# bitfury_power.net
KiCad netlist of a schematic drawn in Altium Designer
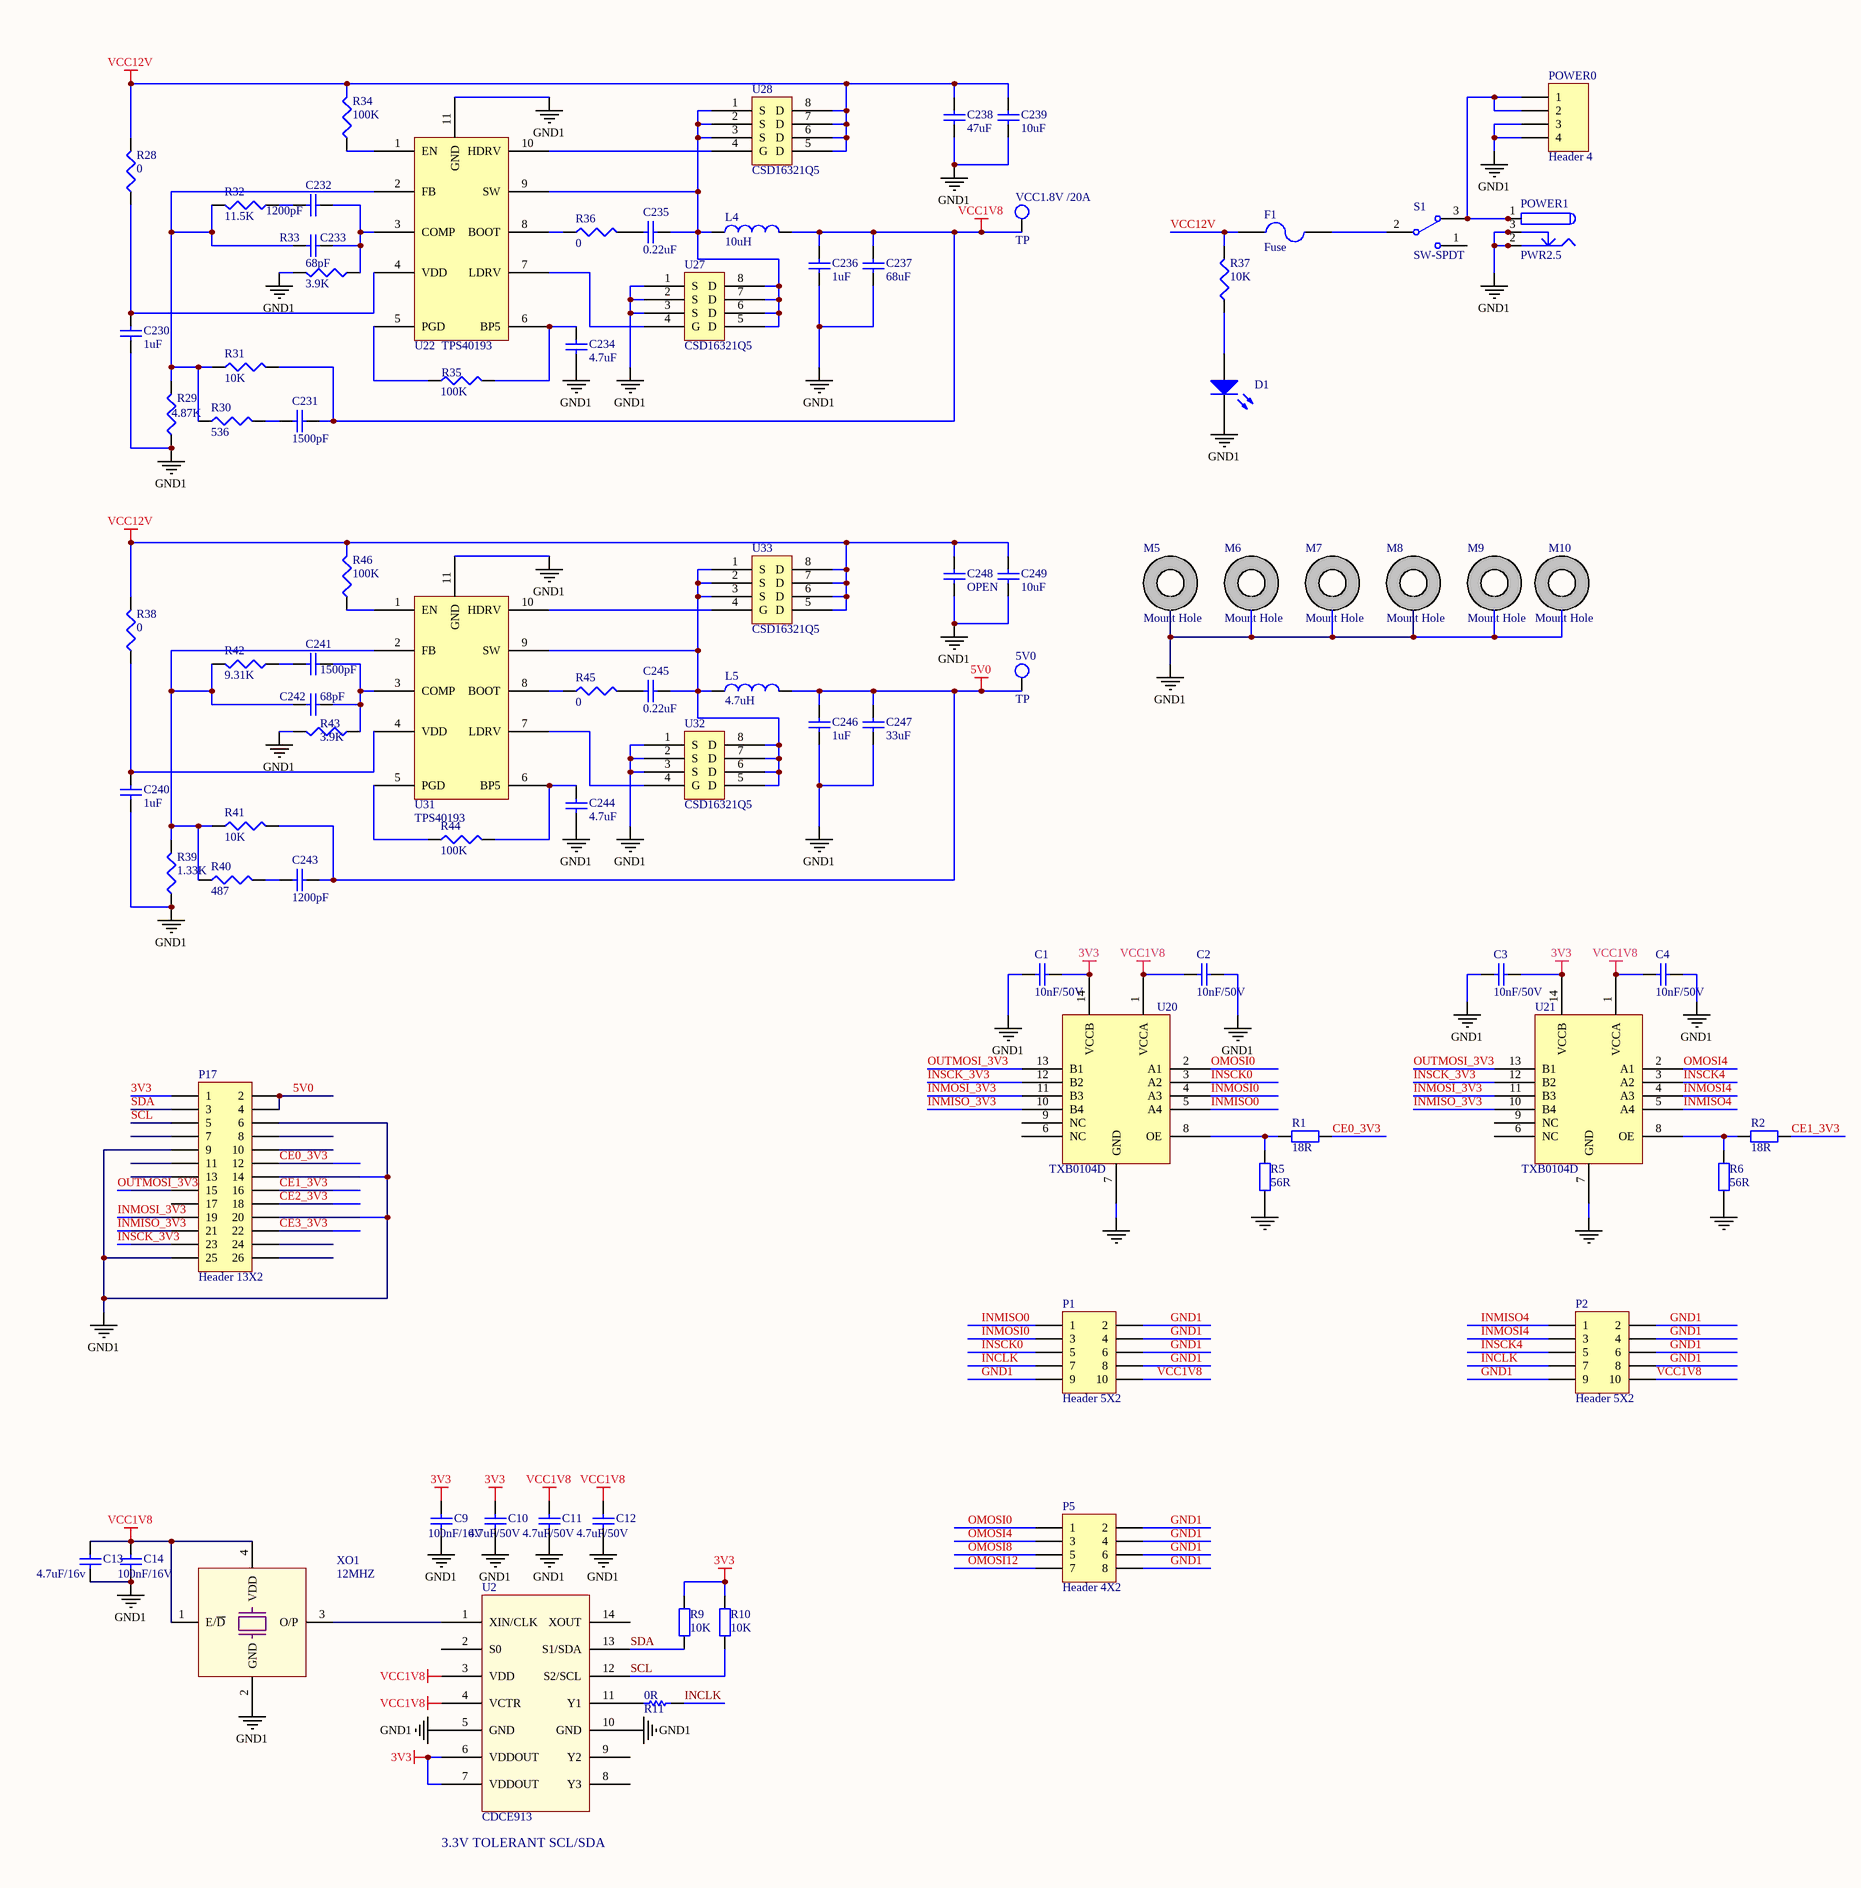
[diagram p0: bitfury_power.SchDoc, left]
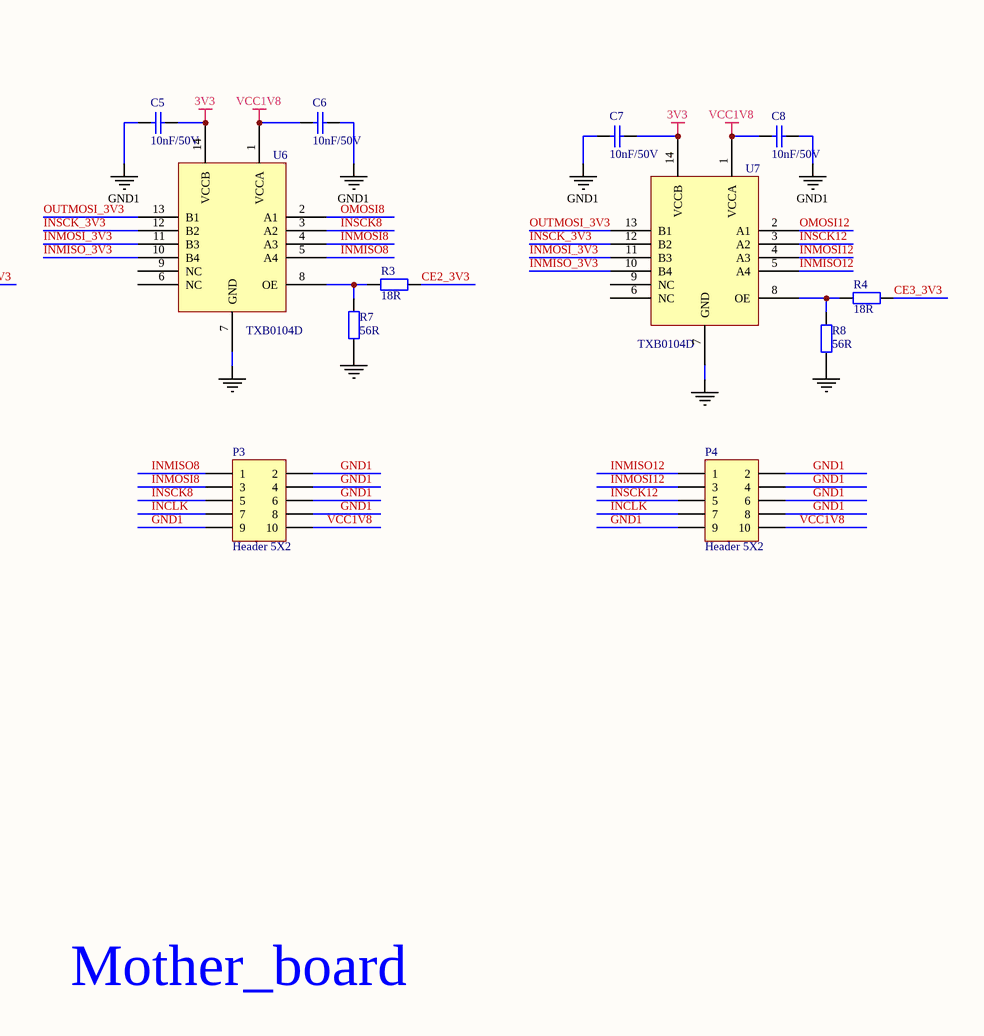
[diagram p1: bitfury_power.SchDoc, right]

(export (version "E")
  (design (tool "Eeschema 10.0.6"))
  (components
    (comp (ref "5V0") (value "TP") (footprint "PIN1") (libsource (lib "S6") (part "TP")))
    (comp (ref "C1")
      (value "10nF/50V")
      (footprint "1608[0603]")
      (description "Capacitor")
      (fields (field (name "PUBLISHER") "Altium Limited"))
      (libsource (lib "Miscellaneous Devices") (part "Cap"))
    )
    (comp (ref "C2")
      (value "10nF/50V")
      (footprint "1608[0603]")
      (description "Capacitor")
      (fields (field (name "PUBLISHER") "Altium Limited"))
      (libsource (lib "Miscellaneous Devices") (part "Cap"))
    )
    (comp (ref "C3")
      (value "10nF/50V")
      (footprint "1608[0603]")
      (description "Capacitor")
      (fields (field (name "PUBLISHER") "Altium Limited"))
      (libsource (lib "Miscellaneous Devices") (part "Cap"))
    )
    (comp (ref "C4")
      (value "10nF/50V")
      (footprint "1608[0603]")
      (description "Capacitor")
      (fields (field (name "PUBLISHER") "Altium Limited"))
      (libsource (lib "Miscellaneous Devices") (part "Cap"))
    )
    (comp (ref "C5")
      (value "10nF/50V")
      (footprint "1608[0603]")
      (description "Capacitor")
      (fields (field (name "PUBLISHER") "Altium Limited"))
      (libsource (lib "Miscellaneous Devices") (part "Cap"))
    )
    (comp (ref "C6")
      (value "10nF/50V")
      (footprint "1608[0603]")
      (description "Capacitor")
      (fields (field (name "PUBLISHER") "Altium Limited"))
      (libsource (lib "Miscellaneous Devices") (part "Cap"))
    )
    (comp (ref "C7")
      (value "10nF/50V")
      (footprint "1608[0603]")
      (description "Capacitor")
      (fields (field (name "PUBLISHER") "Altium Limited"))
      (libsource (lib "Miscellaneous Devices") (part "Cap"))
    )
    (comp (ref "C8")
      (value "10nF/50V")
      (footprint "1608[0603]")
      (description "Capacitor")
      (fields (field (name "PUBLISHER") "Altium Limited"))
      (libsource (lib "Miscellaneous Devices") (part "Cap"))
    )
    (comp (ref "C9")
      (value "100nF/16V")
      (footprint "1608[0603]")
      (description "Capacitor")
      (fields (field (name "PUBLISHER") "Altium Limited"))
      (libsource (lib "Miscellaneous Devices") (part "Cap"))
    )
    (comp (ref "C10")
      (value "4.7uF/50V")
      (footprint "1608[0603]")
      (description "Capacitor")
      (fields (field (name "PUBLISHER") "Altium Limited"))
      (libsource (lib "Miscellaneous Devices") (part "Cap"))
    )
    (comp (ref "C11")
      (value "4.7uF/50V")
      (footprint "1608[0603]")
      (description "Capacitor")
      (fields (field (name "PUBLISHER") "Altium Limited"))
      (libsource (lib "Miscellaneous Devices") (part "Cap"))
    )
    (comp (ref "C12")
      (value "4.7uF/50V")
      (footprint "1608[0603]")
      (description "Capacitor")
      (fields (field (name "PUBLISHER") "Altium Limited"))
      (libsource (lib "Miscellaneous Devices") (part "Cap"))
    )
    (comp (ref "C13")
      (value "4.7uF/16v")
      (footprint "1608[0603]")
      (description "Capacitor")
      (fields (field (name "PUBLISHER") "Altium Limited"))
      (libsource (lib "Miscellaneous Devices") (part "Cap"))
    )
    (comp (ref "C14")
      (value "100nF/16V")
      (footprint "1608[0603]")
      (description "Capacitor")
      (fields (field (name "PUBLISHER") "Altium Limited"))
      (libsource (lib "Miscellaneous Devices") (part "Cap"))
    )
    (comp (ref "C230")
      (value "1uF")
      (footprint "1608[0603]")
      (description "Capacitor")
      (fields (field (name "PUBLISHER") "Altium Limited"))
      (libsource (lib "Miscellaneous Devices") (part "Cap"))
    )
    (comp (ref "C231")
      (value "1500pF")
      (footprint "1608[0603]")
      (description "Capacitor")
      (fields (field (name "PUBLISHER") "Altium Limited"))
      (libsource (lib "Miscellaneous Devices") (part "Cap"))
    )
    (comp (ref "C232")
      (value "1200pF")
      (footprint "1608[0603]")
      (description "Capacitor")
      (fields (field (name "PUBLISHER") "Altium Limited"))
      (libsource (lib "Miscellaneous Devices") (part "Cap"))
    )
    (comp (ref "C233")
      (value "68pF")
      (footprint "1608[0603]")
      (description "Capacitor")
      (fields (field (name "PUBLISHER") "Altium Limited"))
      (libsource (lib "Miscellaneous Devices") (part "Cap"))
    )
    (comp (ref "C234")
      (value "4.7uF")
      (footprint "1608[0603]")
      (description "Capacitor")
      (fields (field (name "PUBLISHER") "Altium Limited"))
      (libsource (lib "Miscellaneous Devices") (part "Cap"))
    )
    (comp (ref "C235")
      (value "0.22uF")
      (footprint "1608[0603]")
      (description "Capacitor")
      (fields (field (name "PUBLISHER") "Altium Limited"))
      (libsource (lib "Miscellaneous Devices") (part "Cap"))
    )
    (comp (ref "C236")
      (value "1uF")
      (footprint "1608[0603]")
      (description "Capacitor")
      (fields (field (name "PUBLISHER") "Altium Limited"))
      (libsource (lib "Miscellaneous Devices") (part "Cap"))
    )
    (comp (ref "C237")
      (value "68uF")
      (footprint "C1210")
      (description "Capacitor")
      (fields (field (name "PUBLISHER") "Altium Limited"))
      (libsource (lib "Miscellaneous Devices") (part "Cap"))
    )
    (comp (ref "C238")
      (value "47uF")
      (footprint "C1210")
      (description "Capacitor")
      (fields (field (name "PUBLISHER") "Altium Limited"))
      (libsource (lib "Miscellaneous Devices") (part "Cap"))
    )
    (comp (ref "C239")
      (value "10uF")
      (footprint "C1210")
      (description "Capacitor")
      (fields (field (name "PUBLISHER") "Altium Limited"))
      (libsource (lib "Miscellaneous Devices") (part "Cap"))
    )
    (comp (ref "C240")
      (value "1uF")
      (footprint "1608[0603]")
      (description "Capacitor")
      (fields (field (name "PUBLISHER") "Altium Limited"))
      (libsource (lib "Miscellaneous Devices") (part "Cap"))
    )
    (comp (ref "C241")
      (value "1500pF")
      (footprint "1608[0603]")
      (description "Capacitor")
      (fields (field (name "PUBLISHER") "Altium Limited"))
      (libsource (lib "Miscellaneous Devices") (part "Cap"))
    )
    (comp (ref "C242")
      (value "68pF")
      (footprint "1608[0603]")
      (description "Capacitor")
      (fields (field (name "PUBLISHER") "Altium Limited"))
      (libsource (lib "Miscellaneous Devices") (part "Cap"))
    )
    (comp (ref "C243")
      (value "1200pF")
      (footprint "1608[0603]")
      (description "Capacitor")
      (fields (field (name "PUBLISHER") "Altium Limited"))
      (libsource (lib "Miscellaneous Devices") (part "Cap"))
    )
    (comp (ref "C244")
      (value "4.7uF")
      (footprint "1608[0603]")
      (description "Capacitor")
      (fields (field (name "PUBLISHER") "Altium Limited"))
      (libsource (lib "Miscellaneous Devices") (part "Cap"))
    )
    (comp (ref "C245")
      (value "0.22uF")
      (footprint "1608[0603]")
      (description "Capacitor")
      (fields (field (name "PUBLISHER") "Altium Limited"))
      (libsource (lib "Miscellaneous Devices") (part "Cap"))
    )
    (comp (ref "C246")
      (value "1uF")
      (footprint "1608[0603]")
      (description "Capacitor")
      (fields (field (name "PUBLISHER") "Altium Limited"))
      (libsource (lib "Miscellaneous Devices") (part "Cap"))
    )
    (comp (ref "C247")
      (value "33uF")
      (footprint "C1210")
      (description "Capacitor")
      (fields (field (name "PUBLISHER") "Altium Limited"))
      (libsource (lib "Miscellaneous Devices") (part "Cap"))
    )
    (comp (ref "C248")
      (value "OPEN")
      (footprint "C1210")
      (description "Capacitor")
      (fields (field (name "PUBLISHER") "Altium Limited"))
      (libsource (lib "Miscellaneous Devices") (part "Cap"))
    )
    (comp (ref "C249")
      (value "10uF")
      (footprint "C1210")
      (description "Capacitor")
      (fields (field (name "PUBLISHER") "Altium Limited"))
      (libsource (lib "Miscellaneous Devices") (part "Cap"))
    )
    (comp (ref "D1")
      (value "~")
      (footprint "CD1608-0603")
      (description "Typical BLUE SiC LED")
      (fields (field (name "PUBLISHER") "Altium Limited"))
      (libsource (lib "Miscellaneous Devices") (part "LED3"))
    )
    (comp (ref "F1")
      (value "Fuse")
      (footprint "RESC5025N1")
      (fields (field (name "PUBLISHER") "Altium Limited"))
      (libsource (lib "Miscellaneous Devices") (part "Fuse 2"))
    )
    (comp (ref "L4")
      (value "10uH")
      (footprint "CDRH104RNP-120")
      (description "Inductor")
      (fields (field (name "PUBLISHER") "Altium Limited"))
      (libsource (lib "Miscellaneous Devices") (part "Inductor"))
    )
    (comp (ref "L5")
      (value "4.7uH")
      (footprint "CDRH104RNP-120")
      (description "Inductor")
      (fields (field (name "PUBLISHER") "Altium Limited"))
      (libsource (lib "Miscellaneous Devices") (part "Inductor"))
    )
    (comp (ref "M5") (value "Mount Hole") (footprint "MHOLE2") (libsource (lib "S6_2") (part "M_Hole")))
    (comp (ref "M6") (value "Mount Hole") (footprint "MHOLE2") (libsource (lib "S6_2") (part "M_Hole")))
    (comp (ref "M7") (value "Mount Hole") (footprint "MHOLE2") (libsource (lib "S6_2") (part "M_Hole")))
    (comp (ref "M8") (value "Mount Hole") (footprint "MHOLE2") (libsource (lib "S6_2") (part "M_Hole")))
    (comp (ref "M9") (value "Mount Hole") (footprint "MHOLE2") (libsource (lib "S6_2") (part "M_Hole")))
    (comp (ref "M10") (value "Mount Hole") (footprint "MHOLE2") (libsource (lib "S6_2") (part "M_Hole")))
    (comp (ref "P1")
      (value "Header 5X2")
      (footprint "HDR2X5")
      (description "Header, 5-Pin, Dual row")
      (fields (field (name "PUBLISHER") "Altium Limited"))
      (libsource (lib "Miscellaneous Connectors") (part "Header 5X2"))
    )
    (comp (ref "P2")
      (value "Header 5X2")
      (footprint "HDR2X5")
      (description "Header, 5-Pin, Dual row")
      (fields (field (name "PUBLISHER") "Altium Limited"))
      (libsource (lib "Miscellaneous Connectors") (part "Header 5X2"))
    )
    (comp (ref "P3")
      (value "Header 5X2")
      (footprint "HDR2X5")
      (description "Header, 5-Pin, Dual row")
      (fields (field (name "PUBLISHER") "Altium Limited"))
      (libsource (lib "Miscellaneous Connectors") (part "Header 5X2"))
    )
    (comp (ref "P4")
      (value "Header 5X2")
      (footprint "HDR2X5")
      (description "Header, 5-Pin, Dual row")
      (fields (field (name "PUBLISHER") "Altium Limited"))
      (libsource (lib "Miscellaneous Connectors") (part "Header 5X2"))
    )
    (comp (ref "P5")
      (value "Header 4X2")
      (footprint "HDR2X4")
      (description "Header, 4-Pin, Dual row")
      (fields (field (name "PUBLISHER") "Altium Limited"))
      (libsource (lib "Miscellaneous Connectors") (part "Header 4X2"))
    )
    (comp (ref "P17")
      (value "Header 13X2")
      (footprint "HDR2X13")
      (description "Header, 13-Pin, Dual row")
      (fields (field (name "PUBLISHER") "Altium Limited"))
      (libsource (lib "Miscellaneous Connectors") (part "Header 13X2"))
    )
    (comp (ref "POWER0")
      (value "Header 4")
      (footprint "SIP4")
      (description "Header, 4-Pin")
      (fields (field (name "PUBLISHER") "Altium Limited"))
      (libsource (lib "Miscellaneous Connectors") (part "Header 4"))
    )
    (comp (ref "POWER1")
      (value "PWR2.5")
      (footprint "KLD-0202")
      (description "Low Voltage Power Supply Connector")
      (fields (field (name "PUBLISHER") "Altium Limited"))
      (libsource (lib "Miscellaneous Connectors") (part "PWR2.5"))
    )
    (comp (ref "R1")
      (value "18R")
      (footprint "6-0805_L")
      (description "Resistor")
      (fields (field (name "PUBLISHER") "Altium Limited"))
      (libsource (lib "") (part "Res2_1"))
    )
    (comp (ref "R2")
      (value "18R")
      (footprint "6-0805_L")
      (description "Resistor")
      (fields (field (name "PUBLISHER") "Altium Limited"))
      (libsource (lib "") (part "Res2_1"))
    )
    (comp (ref "R3")
      (value "18R")
      (footprint "6-0805_L")
      (description "Resistor")
      (fields (field (name "PUBLISHER") "Altium Limited"))
      (libsource (lib "") (part "Res2_1"))
    )
    (comp (ref "R4")
      (value "18R")
      (footprint "6-0805_L")
      (description "Resistor")
      (fields (field (name "PUBLISHER") "Altium Limited"))
      (libsource (lib "") (part "Res2_1"))
    )
    (comp (ref "R5")
      (value "56R")
      (footprint "6-0805_L")
      (description "Resistor")
      (fields (field (name "PUBLISHER") "Altium Limited"))
      (libsource (lib "Miscellaneous Devices") (part "Res2"))
    )
    (comp (ref "R6")
      (value "56R")
      (footprint "6-0805_L")
      (description "Resistor")
      (fields (field (name "PUBLISHER") "Altium Limited"))
      (libsource (lib "Miscellaneous Devices") (part "Res2"))
    )
    (comp (ref "R7")
      (value "56R")
      (footprint "6-0805_L")
      (description "Resistor")
      (fields (field (name "PUBLISHER") "Altium Limited"))
      (libsource (lib "Miscellaneous Devices") (part "Res2"))
    )
    (comp (ref "R8")
      (value "56R")
      (footprint "6-0805_L")
      (description "Resistor")
      (fields (field (name "PUBLISHER") "Altium Limited"))
      (libsource (lib "Miscellaneous Devices") (part "Res2"))
    )
    (comp (ref "R9")
      (value "10K")
      (footprint "6-0805_L")
      (description "Resistor")
      (fields (field (name "PUBLISHER") "Altium Limited"))
      (libsource (lib "") (part "Res2_2"))
    )
    (comp (ref "R10")
      (value "10K")
      (footprint "6-0805_L")
      (description "Resistor")
      (fields (field (name "PUBLISHER") "Altium Limited"))
      (libsource (lib "Miscellaneous Devices") (part "Res2"))
    )
    (comp (ref "R11")
      (value "0R")
      (footprint "6-0805_L")
      (fields (field (name "PART #") "RC1608J000CS"))
      (libsource (lib "DANS SMALL COMPS") (part "default res SML 1"))
    )
    (comp (ref "R28")
      (value "0")
      (footprint "6-0805_L")
      (description "Resistor")
      (fields (field (name "PUBLISHER") "Altium Limited"))
      (libsource (lib "Miscellaneous Devices") (part "Res3"))
    )
    (comp (ref "R29")
      (value "4.87K")
      (footprint "6-0805_L")
      (description "Resistor")
      (fields (field (name "PUBLISHER") "Altium Limited"))
      (libsource (lib "Miscellaneous Devices") (part "Res3"))
    )
    (comp (ref "R30")
      (value "536")
      (footprint "6-0805_L")
      (description "Resistor")
      (fields (field (name "PUBLISHER") "Altium Limited"))
      (libsource (lib "Miscellaneous Devices") (part "Res3"))
    )
    (comp (ref "R31")
      (value "10K")
      (footprint "6-0805_L")
      (description "Resistor")
      (fields (field (name "PUBLISHER") "Altium Limited"))
      (libsource (lib "Miscellaneous Devices") (part "Res3"))
    )
    (comp (ref "R32")
      (value "11.5K")
      (footprint "6-0805_L")
      (description "Resistor")
      (fields (field (name "PUBLISHER") "Altium Limited"))
      (libsource (lib "Miscellaneous Devices") (part "Res3"))
    )
    (comp (ref "R33")
      (value "3.9K")
      (footprint "6-0805_L")
      (description "Resistor")
      (fields (field (name "PUBLISHER") "Altium Limited"))
      (libsource (lib "Miscellaneous Devices") (part "Res3"))
    )
    (comp (ref "R34")
      (value "100K")
      (footprint "6-0805_L")
      (description "Resistor")
      (fields (field (name "PUBLISHER") "Altium Limited"))
      (libsource (lib "Miscellaneous Devices") (part "Res3"))
    )
    (comp (ref "R35")
      (value "100K")
      (footprint "6-0805_L")
      (description "Resistor")
      (fields (field (name "PUBLISHER") "Altium Limited"))
      (libsource (lib "Miscellaneous Devices") (part "Res3"))
    )
    (comp (ref "R36")
      (value "0")
      (footprint "6-0805_L")
      (description "Resistor")
      (fields (field (name "PUBLISHER") "Altium Limited"))
      (libsource (lib "Miscellaneous Devices") (part "Res3"))
    )
    (comp (ref "R37")
      (value "10K")
      (footprint "J1-0603")
      (description "Resistor")
      (fields (field (name "PUBLISHER") "Altium Limited"))
      (libsource (lib "Miscellaneous Devices") (part "Res3"))
    )
    (comp (ref "R38")
      (value "0")
      (footprint "6-0805_L")
      (description "Resistor")
      (fields (field (name "PUBLISHER") "Altium Limited"))
      (libsource (lib "Miscellaneous Devices") (part "Res3"))
    )
    (comp (ref "R39")
      (value "1.33K")
      (footprint "6-0805_L")
      (description "Resistor")
      (fields (field (name "PUBLISHER") "Altium Limited"))
      (libsource (lib "Miscellaneous Devices") (part "Res3"))
    )
    (comp (ref "R40")
      (value "487")
      (footprint "6-0805_L")
      (description "Resistor")
      (fields (field (name "PUBLISHER") "Altium Limited"))
      (libsource (lib "Miscellaneous Devices") (part "Res3"))
    )
    (comp (ref "R41")
      (value "10K")
      (footprint "6-0805_L")
      (description "Resistor")
      (fields (field (name "PUBLISHER") "Altium Limited"))
      (libsource (lib "Miscellaneous Devices") (part "Res3"))
    )
    (comp (ref "R42")
      (value "9.31K")
      (footprint "6-0805_L")
      (description "Resistor")
      (fields (field (name "PUBLISHER") "Altium Limited"))
      (libsource (lib "Miscellaneous Devices") (part "Res3"))
    )
    (comp (ref "R43")
      (value "3.9K")
      (footprint "6-0805_L")
      (description "Resistor")
      (fields (field (name "PUBLISHER") "Altium Limited"))
      (libsource (lib "Miscellaneous Devices") (part "Res3"))
    )
    (comp (ref "R44")
      (value "100K")
      (footprint "6-0805_L")
      (description "Resistor")
      (fields (field (name "PUBLISHER") "Altium Limited"))
      (libsource (lib "Miscellaneous Devices") (part "Res3"))
    )
    (comp (ref "R45")
      (value "0")
      (footprint "6-0805_L")
      (description "Resistor")
      (fields (field (name "PUBLISHER") "Altium Limited"))
      (libsource (lib "Miscellaneous Devices") (part "Res3"))
    )
    (comp (ref "R46")
      (value "100K")
      (footprint "6-0805_L")
      (description "Resistor")
      (fields (field (name "PUBLISHER") "Altium Limited"))
      (libsource (lib "Miscellaneous Devices") (part "Res3"))
    )
    (comp (ref "S1")
      (value "SW-SPDT")
      (footprint "SW3_S1")
      (description "SPDT Subminiature Toggle Switch, Right Angle Mounting, Vertical Actuation")
      (fields (field (name "PUBLISHER") "Altium Limited"))
      (libsource (lib "Miscellaneous Devices") (part "SW-SPDT"))
    )
    (comp (ref "U2")
      (value "CDCE913")
      (footprint "TSSOP14 N")
      (description "CLKC GEN")
      (fields (field (name "PART #") "CDCEL913PW"))
      (libsource (lib "RFS") (part "CDCEL913"))
    )
    (comp (ref "U6")
      (value "TXB0104D")
      (footprint "TXB0104-sop14")
      (libsource (lib "Schlib1") (part "TXB0104D"))
    )
    (comp (ref "U7")
      (value "TXB0104D")
      (footprint "TXB0104-sop14")
      (libsource (lib "Schlib1") (part "TXB0104D"))
    )
    (comp (ref "U20")
      (value "TXB0104D")
      (footprint "TXB0104-sop14")
      (libsource (lib "Schlib1") (part "TXB0104D"))
    )
    (comp (ref "U21")
      (value "TXB0104D")
      (footprint "TXB0104-sop14")
      (libsource (lib "Schlib1") (part "TXB0104D"))
    )
    (comp (ref "U22") (value "TPS40193") (libsource (lib "Schlib1") (part "TPS40193")))
    (comp (ref "U27")
      (value "CSD16321Q5")
      (footprint "CSD16321")
      (libsource (lib "Schlib1") (part "CSD16321Q5"))
    )
    (comp (ref "U28")
      (value "CSD16321Q5")
      (footprint "CSD16321")
      (libsource (lib "Schlib1") (part "CSD16321Q5"))
    )
    (comp (ref "U31") (value "TPS40193") (footprint "SON-N10") (libsource (lib "Schlib1") (part "TPS40193")))
    (comp (ref "U32")
      (value "CSD16321Q5")
      (footprint "CSD16321")
      (libsource (lib "Schlib1") (part "CSD16321Q5"))
    )
    (comp (ref "U33")
      (value "CSD16321Q5")
      (footprint "CSD16321")
      (libsource (lib "Schlib1") (part "CSD16321Q5"))
    )
    (comp (ref "VCC1.8V /20A") (value "TP") (footprint "PIN1") (libsource (lib "S6") (part "TP")))
    (comp (ref "XO1")
      (value "12MHZ")
      (footprint "OSC 7.5x5.2")
      (description "OSCILLATOR")
      (fields (field (name "PART #") "CB3LV-3C-12M0000"))
      (libsource (lib "DIGITAL AUDIO") (part "CLK OSC XTL"))
    )
  )
  (nets
    (net (code "1") (name "/CE0_3V3") (class "Default")
      (node (ref "P17") (pin "12") (pinfunction "12_12") (pintype "passive"))
      (node (ref "R1") (pin "2") (pinfunction "2_2") (pintype "passive"))
    )
    (net (code "2") (name "/CE1_3V3") (class "Default")
      (node (ref "P17") (pin "16") (pinfunction "16_16") (pintype "passive"))
      (node (ref "R2") (pin "2") (pinfunction "2_2") (pintype "passive"))
    )
    (net (code "3") (name "/CE2_3V3") (class "Default")
      (node (ref "P17") (pin "18") (pinfunction "18_18") (pintype "passive"))
      (node (ref "R3") (pin "2") (pinfunction "2_2") (pintype "passive"))
    )
    (net (code "4") (name "/CE3_3V3") (class "Default")
      (node (ref "P17") (pin "22") (pinfunction "22_22") (pintype "passive"))
      (node (ref "R4") (pin "2") (pinfunction "2_2") (pintype "passive"))
    )
    (net (code "5") (name "/INCLK") (class "Default")
      (node (ref "P1") (pin "7") (pinfunction "7_7") (pintype "passive"))
      (node (ref "P2") (pin "7") (pinfunction "7_7") (pintype "passive"))
      (node (ref "P3") (pin "7") (pinfunction "7_7") (pintype "passive"))
      (node (ref "P4") (pin "7") (pinfunction "7_7") (pintype "passive"))
      (node (ref "R11") (pin "1") (pinfunction "1_1") (pintype "passive"))
    )
    (net (code "6") (name "/INMISO0") (class "Default")
      (node (ref "P1") (pin "1") (pinfunction "1_1") (pintype "passive"))
      (node (ref "U20") (pin "5") (pinfunction "A4_5") (pintype "open_collector"))
    )
    (net (code "7") (name "/INMISO4") (class "Default")
      (node (ref "P2") (pin "1") (pinfunction "1_1") (pintype "passive"))
      (node (ref "U21") (pin "5") (pinfunction "A4_5") (pintype "open_collector"))
    )
    (net (code "8") (name "/INMISO8") (class "Default")
      (node (ref "P3") (pin "1") (pinfunction "1_1") (pintype "passive"))
      (node (ref "U6") (pin "5") (pinfunction "A4_5") (pintype "open_collector"))
    )
    (net (code "9") (name "/INMISO12") (class "Default")
      (node (ref "P4") (pin "1") (pinfunction "1_1") (pintype "passive"))
      (node (ref "U7") (pin "5") (pinfunction "A4_5") (pintype "open_collector"))
    )
    (net (code "10") (name "/INMISO_3V3") (class "Default")
      (node (ref "P17") (pin "21") (pinfunction "21_21") (pintype "passive"))
      (node (ref "U20") (pin "10") (pinfunction "B4_10") (pintype "open_collector"))
      (node (ref "U21") (pin "10") (pinfunction "B4_10") (pintype "open_collector"))
      (node (ref "U6") (pin "10") (pinfunction "B4_10") (pintype "open_collector"))
      (node (ref "U7") (pin "10") (pinfunction "B4_10") (pintype "open_collector"))
    )
    (net (code "11") (name "/INMOSI0") (class "Default")
      (node (ref "P1") (pin "3") (pinfunction "3_3") (pintype "passive"))
      (node (ref "U20") (pin "4") (pinfunction "A3_4") (pintype "open_collector"))
    )
    (net (code "12") (name "/INMOSI4") (class "Default")
      (node (ref "P2") (pin "3") (pinfunction "3_3") (pintype "passive"))
      (node (ref "U21") (pin "4") (pinfunction "A3_4") (pintype "open_collector"))
    )
    (net (code "13") (name "/INMOSI8") (class "Default")
      (node (ref "P3") (pin "3") (pinfunction "3_3") (pintype "passive"))
      (node (ref "U6") (pin "4") (pinfunction "A3_4") (pintype "open_collector"))
    )
    (net (code "14") (name "/INMOSI12") (class "Default")
      (node (ref "P4") (pin "3") (pinfunction "3_3") (pintype "passive"))
      (node (ref "U7") (pin "4") (pinfunction "A3_4") (pintype "open_collector"))
    )
    (net (code "15") (name "/INMOSI_3V3") (class "Default")
      (node (ref "P17") (pin "19") (pinfunction "19_19") (pintype "passive"))
      (node (ref "U20") (pin "11") (pinfunction "B3_11") (pintype "open_collector"))
      (node (ref "U21") (pin "11") (pinfunction "B3_11") (pintype "open_collector"))
      (node (ref "U6") (pin "11") (pinfunction "B3_11") (pintype "open_collector"))
      (node (ref "U7") (pin "11") (pinfunction "B3_11") (pintype "open_collector"))
    )
    (net (code "16") (name "/INSCK0") (class "Default")
      (node (ref "P1") (pin "5") (pinfunction "5_5") (pintype "passive"))
      (node (ref "U20") (pin "3") (pinfunction "A2_3") (pintype "open_collector"))
    )
    (net (code "17") (name "/INSCK4") (class "Default")
      (node (ref "P2") (pin "5") (pinfunction "5_5") (pintype "passive"))
      (node (ref "U21") (pin "3") (pinfunction "A2_3") (pintype "open_collector"))
    )
    (net (code "18") (name "/INSCK8") (class "Default")
      (node (ref "P3") (pin "5") (pinfunction "5_5") (pintype "passive"))
      (node (ref "U6") (pin "3") (pinfunction "A2_3") (pintype "open_collector"))
    )
    (net (code "19") (name "/INSCK12") (class "Default")
      (node (ref "P4") (pin "5") (pinfunction "5_5") (pintype "passive"))
      (node (ref "U7") (pin "3") (pinfunction "A2_3") (pintype "open_collector"))
    )
    (net (code "20") (name "/INSCK_3V3") (class "Default")
      (node (ref "P17") (pin "23") (pinfunction "23_23") (pintype "passive"))
      (node (ref "U20") (pin "12") (pinfunction "B2_12") (pintype "open_collector"))
      (node (ref "U21") (pin "12") (pinfunction "B2_12") (pintype "open_collector"))
      (node (ref "U6") (pin "12") (pinfunction "B2_12") (pintype "open_collector"))
      (node (ref "U7") (pin "12") (pinfunction "B2_12") (pintype "open_collector"))
    )
    (net (code "21") (name "/OMOSI0") (class "Default")
      (node (ref "P5") (pin "1") (pinfunction "1_1") (pintype "passive"))
      (node (ref "U20") (pin "2") (pinfunction "A1_2") (pintype "open_collector"))
    )
    (net (code "22") (name "/OMOSI4") (class "Default")
      (node (ref "P5") (pin "3") (pinfunction "3_3") (pintype "passive"))
      (node (ref "U21") (pin "2") (pinfunction "A1_2") (pintype "open_collector"))
    )
    (net (code "23") (name "/OMOSI8") (class "Default")
      (node (ref "P5") (pin "5") (pinfunction "5_5") (pintype "passive"))
      (node (ref "U6") (pin "2") (pinfunction "A1_2") (pintype "open_collector"))
    )
    (net (code "24") (name "/OMOSI12") (class "Default")
      (node (ref "P5") (pin "7") (pinfunction "7_7") (pintype "passive"))
      (node (ref "U7") (pin "2") (pinfunction "A1_2") (pintype "open_collector"))
    )
    (net (code "25") (name "/OUTMOSI_3V3") (class "Default")
      (node (ref "P17") (pin "15") (pinfunction "15_15") (pintype "passive"))
      (node (ref "U20") (pin "13") (pinfunction "B1_13") (pintype "open_collector"))
      (node (ref "U21") (pin "13") (pinfunction "B1_13") (pintype "open_collector"))
      (node (ref "U6") (pin "13") (pinfunction "B1_13") (pintype "open_collector"))
      (node (ref "U7") (pin "13") (pinfunction "B1_13") (pintype "open_collector"))
    )
    (net (code "26") (name "/SCL") (class "Default")
      (node (ref "P17") (pin "5") (pinfunction "5_5") (pintype "passive"))
      (node (ref "R10") (pin "1") (pinfunction "1_1") (pintype "passive"))
      (node (ref "U2") (pin "12") (pinfunction "S2/SCL_12") (pintype "passive"))
    )
    (net (code "27") (name "/SDA") (class "Default")
      (node (ref "P17") (pin "3") (pinfunction "3_3") (pintype "passive"))
      (node (ref "R9") (pin "2") (pinfunction "2_2") (pintype "passive"))
      (node (ref "U2") (pin "13") (pinfunction "S1/SDA_13") (pintype "passive"))
    )
    (net (code "28") (name "3V3") (class "Default")
      (node (ref "C1") (pin "2") (pinfunction "2_2") (pintype "passive"))
      (node (ref "C10") (pin "2") (pinfunction "2_2") (pintype "passive"))
      (node (ref "C3") (pin "2") (pinfunction "2_2") (pintype "passive"))
      (node (ref "C5") (pin "2") (pinfunction "2_2") (pintype "passive"))
      (node (ref "C7") (pin "2") (pinfunction "2_2") (pintype "passive"))
      (node (ref "C9") (pin "2") (pinfunction "2_2") (pintype "passive"))
      (node (ref "P17") (pin "1") (pinfunction "1_1") (pintype "passive"))
      (node (ref "R10") (pin "2") (pinfunction "2_2") (pintype "passive"))
      (node (ref "R9") (pin "1") (pinfunction "1_1") (pintype "passive"))
      (node (ref "U2") (pin "6") (pinfunction "VDDOUT_6") (pintype "passive"))
      (node (ref "U2") (pin "7") (pinfunction "VDDOUT_7") (pintype "passive"))
      (node (ref "U20") (pin "14") (pinfunction "VCCB_14") (pintype "open_collector"))
      (node (ref "U21") (pin "14") (pinfunction "VCCB_14") (pintype "open_collector"))
      (node (ref "U6") (pin "14") (pinfunction "VCCB_14") (pintype "open_collector"))
      (node (ref "U7") (pin "14") (pinfunction "VCCB_14") (pintype "open_collector"))
    )
    (net (code "29") (name "5V0") (class "Default")
      (node (ref "5V0") (pin "1") (pinfunction "TP_1") (pintype "passive"))
      (node (ref "C243") (pin "2") (pinfunction "2_2") (pintype "passive"))
      (node (ref "C246") (pin "2") (pinfunction "2_2") (pintype "passive"))
      (node (ref "C247") (pin "2") (pinfunction "2_2") (pintype "passive"))
      (node (ref "L5") (pin "2") (pinfunction "2_2") (pintype "passive"))
      (node (ref "P17") (pin "2") (pinfunction "2_2") (pintype "passive"))
      (node (ref "P17") (pin "4") (pinfunction "4_4") (pintype "passive"))
      (node (ref "R41") (pin "2") (pinfunction "2_2") (pintype "passive"))
    )
    (net (code "30") (name "GND1") (class "Default")
      (node (ref "C1") (pin "1") (pinfunction "1_1") (pintype "passive"))
      (node (ref "C10") (pin "1") (pinfunction "1_1") (pintype "passive"))
      (node (ref "C11") (pin "1") (pinfunction "1_1") (pintype "passive"))
      (node (ref "C12") (pin "1") (pinfunction "1_1") (pintype "passive"))
      (node (ref "C13") (pin "2") (pinfunction "2_2") (pintype "passive"))
      (node (ref "C14") (pin "1") (pinfunction "1_1") (pintype "passive"))
      (node (ref "C2") (pin "2") (pinfunction "2_2") (pintype "passive"))
      (node (ref "C230") (pin "1") (pinfunction "1_1") (pintype "passive"))
      (node (ref "C234") (pin "1") (pinfunction "1_1") (pintype "passive"))
      (node (ref "C236") (pin "1") (pinfunction "1_1") (pintype "passive"))
      (node (ref "C237") (pin "1") (pinfunction "1_1") (pintype "passive"))
      (node (ref "C238") (pin "1") (pinfunction "1_1") (pintype "passive"))
      (node (ref "C239") (pin "1") (pinfunction "1_1") (pintype "passive"))
      (node (ref "C240") (pin "1") (pinfunction "1_1") (pintype "passive"))
      (node (ref "C244") (pin "1") (pinfunction "1_1") (pintype "passive"))
      (node (ref "C246") (pin "1") (pinfunction "1_1") (pintype "passive"))
      (node (ref "C247") (pin "1") (pinfunction "1_1") (pintype "passive"))
      (node (ref "C248") (pin "1") (pinfunction "1_1") (pintype "passive"))
      (node (ref "C249") (pin "1") (pinfunction "1_1") (pintype "passive"))
      (node (ref "C3") (pin "1") (pinfunction "1_1") (pintype "passive"))
      (node (ref "C4") (pin "2") (pinfunction "2_2") (pintype "passive"))
      (node (ref "C5") (pin "1") (pinfunction "1_1") (pintype "passive"))
      (node (ref "C6") (pin "2") (pinfunction "2_2") (pintype "passive"))
      (node (ref "C7") (pin "1") (pinfunction "1_1") (pintype "passive"))
      (node (ref "C8") (pin "2") (pinfunction "2_2") (pintype "passive"))
      (node (ref "C9") (pin "1") (pinfunction "1_1") (pintype "passive"))
      (node (ref "D1") (pin "2") (pinfunction "K_2") (pintype "passive"))
      (node (ref "M10") (pin "0") (pinfunction "PIN_0") (pintype "power_in"))
      (node (ref "M5") (pin "0") (pinfunction "PIN_0") (pintype "power_in"))
      (node (ref "M6") (pin "0") (pinfunction "PIN_0") (pintype "power_in"))
      (node (ref "M7") (pin "0") (pinfunction "PIN_0") (pintype "power_in"))
      (node (ref "M8") (pin "0") (pinfunction "PIN_0") (pintype "power_in"))
      (node (ref "M9") (pin "0") (pinfunction "PIN_0") (pintype "power_in"))
      (node (ref "P1") (pin "2") (pinfunction "2_2") (pintype "passive"))
      (node (ref "P1") (pin "4") (pinfunction "4_4") (pintype "passive"))
      (node (ref "P1") (pin "6") (pinfunction "6_6") (pintype "passive"))
      (node (ref "P1") (pin "8") (pinfunction "8_8") (pintype "passive"))
      (node (ref "P1") (pin "9") (pinfunction "9_9") (pintype "passive"))
      (node (ref "P17") (pin "14") (pinfunction "14_14") (pintype "passive"))
      (node (ref "P17") (pin "20") (pinfunction "20_20") (pintype "passive"))
      (node (ref "P17") (pin "25") (pinfunction "25_25") (pintype "passive"))
      (node (ref "P17") (pin "6") (pinfunction "6_6") (pintype "passive"))
      (node (ref "P17") (pin "9") (pinfunction "9_9") (pintype "passive"))
      (node (ref "P2") (pin "2") (pinfunction "2_2") (pintype "passive"))
      (node (ref "P2") (pin "4") (pinfunction "4_4") (pintype "passive"))
      (node (ref "P2") (pin "6") (pinfunction "6_6") (pintype "passive"))
      (node (ref "P2") (pin "8") (pinfunction "8_8") (pintype "passive"))
      (node (ref "P2") (pin "9") (pinfunction "9_9") (pintype "passive"))
      (node (ref "P3") (pin "2") (pinfunction "2_2") (pintype "passive"))
      (node (ref "P3") (pin "4") (pinfunction "4_4") (pintype "passive"))
      (node (ref "P3") (pin "6") (pinfunction "6_6") (pintype "passive"))
      (node (ref "P3") (pin "8") (pinfunction "8_8") (pintype "passive"))
      (node (ref "P3") (pin "9") (pinfunction "9_9") (pintype "passive"))
      (node (ref "P4") (pin "2") (pinfunction "2_2") (pintype "passive"))
      (node (ref "P4") (pin "4") (pinfunction "4_4") (pintype "passive"))
      (node (ref "P4") (pin "6") (pinfunction "6_6") (pintype "passive"))
      (node (ref "P4") (pin "8") (pinfunction "8_8") (pintype "passive"))
      (node (ref "P4") (pin "9") (pinfunction "9_9") (pintype "passive"))
      (node (ref "P5") (pin "2") (pinfunction "2_2") (pintype "passive"))
      (node (ref "P5") (pin "4") (pinfunction "4_4") (pintype "passive"))
      (node (ref "P5") (pin "6") (pinfunction "6_6") (pintype "passive"))
      (node (ref "P5") (pin "8") (pinfunction "8_8") (pintype "passive"))
      (node (ref "POWER0") (pin "3") (pinfunction "3_3") (pintype "passive"))
      (node (ref "POWER0") (pin "4") (pinfunction "4_4") (pintype "passive"))
      (node (ref "POWER1") (pin "2") (pinfunction "2_2") (pintype "power_in"))
      (node (ref "POWER1") (pin "2A") (pinfunction "2A_2A") (pintype "power_in"))
      (node (ref "POWER1") (pin "2B") (pinfunction "2B_2B") (pintype "power_in"))
      (node (ref "POWER1") (pin "3") (pinfunction "3_3") (pintype "power_in"))
      (node (ref "POWER1") (pin "3A") (pinfunction "3A_3A") (pintype "power_in"))
      (node (ref "POWER1") (pin "3B") (pinfunction "3B_3B") (pintype "power_in"))
      (node (ref "R29") (pin "1") (pinfunction "1_1") (pintype "passive"))
      (node (ref "R33") (pin "2") (pinfunction "2_2") (pintype "passive"))
      (node (ref "R39") (pin "1") (pinfunction "1_1") (pintype "passive"))
      (node (ref "R43") (pin "2") (pinfunction "2_2") (pintype "passive"))
      (node (ref "R5") (pin "1") (pinfunction "1_1") (pintype "passive"))
      (node (ref "R6") (pin "1") (pinfunction "1_1") (pintype "passive"))
      (node (ref "R7") (pin "1") (pinfunction "1_1") (pintype "passive"))
      (node (ref "R8") (pin "1") (pinfunction "1_1") (pintype "passive"))
      (node (ref "U2") (pin "10") (pinfunction "GND_10") (pintype "passive"))
      (node (ref "U2") (pin "5") (pinfunction "GND_5") (pintype "passive"))
      (node (ref "U20") (pin "7") (pinfunction "GND_7") (pintype "open_collector"))
      (node (ref "U21") (pin "7") (pinfunction "GND_7") (pintype "open_collector"))
      (node (ref "U22") (pin "11") (pinfunction "GND_11") (pintype "open_collector"))
      (node (ref "U27") (pin "1") (pinfunction "S_1") (pintype "open_collector"))
      (node (ref "U27") (pin "2") (pinfunction "S_2") (pintype "open_collector"))
      (node (ref "U27") (pin "3") (pinfunction "S_3") (pintype "open_collector"))
      (node (ref "U31") (pin "11") (pinfunction "GND_11") (pintype "open_collector"))
      (node (ref "U32") (pin "1") (pinfunction "S_1") (pintype "open_collector"))
      (node (ref "U32") (pin "2") (pinfunction "S_2") (pintype "open_collector"))
      (node (ref "U32") (pin "3") (pinfunction "S_3") (pintype "open_collector"))
      (node (ref "U6") (pin "7") (pinfunction "GND_7") (pintype "open_collector"))
      (node (ref "U7") (pin "7") (pinfunction "GND_7") (pintype "open_collector"))
      (node (ref "XO1") (pin "2") (pinfunction "GND_2") (pintype "passive"))
    )
    (net (code "31") (name "Net-(C231-Pad1)") (class "Default")
      (node (ref "C231") (pin "1") (pinfunction "1_1") (pintype "passive"))
      (node (ref "R30") (pin "2") (pinfunction "2_2") (pintype "passive"))
    )
    (net (code "32") (name "Net-(C232-Pad1)") (class "Default")
      (node (ref "C232") (pin "1") (pinfunction "1_1") (pintype "passive"))
      (node (ref "R32") (pin "1") (pinfunction "1_1") (pintype "passive"))
    )
    (net (code "33") (name "Net-(C235-Pad2)") (class "Default")
      (node (ref "C235") (pin "2") (pinfunction "2_2") (pintype "passive"))
      (node (ref "R36") (pin "2") (pinfunction "2_2") (pintype "passive"))
    )
    (net (code "34") (name "Net-(C241-Pad1)") (class "Default")
      (node (ref "C241") (pin "1") (pinfunction "1_1") (pintype "passive"))
      (node (ref "R42") (pin "1") (pinfunction "1_1") (pintype "passive"))
    )
    (net (code "35") (name "Net-(C243-Pad1)") (class "Default")
      (node (ref "C243") (pin "1") (pinfunction "1_1") (pintype "passive"))
      (node (ref "R40") (pin "2") (pinfunction "2_2") (pintype "passive"))
    )
    (net (code "36") (name "Net-(C245-Pad2)") (class "Default")
      (node (ref "C245") (pin "2") (pinfunction "2_2") (pintype "passive"))
      (node (ref "R45") (pin "2") (pinfunction "2_2") (pintype "passive"))
    )
    (net (code "37") (name "Net-(D1-A)") (class "Default")
      (node (ref "D1") (pin "1") (pinfunction "A_1") (pintype "passive"))
      (node (ref "R37") (pin "1") (pinfunction "1_1") (pintype "passive"))
    )
    (net (code "38") (name "Net-(F1-Pad2)") (class "Default")
      (node (ref "F1") (pin "2") (pinfunction "2_2") (pintype "passive"))
      (node (ref "S1") (pin "2") (pinfunction "2_2") (pintype "passive"))
    )
    (net (code "39") (name "Net-(POWER0-Pad1)") (class "Default")
      (node (ref "POWER0") (pin "1") (pinfunction "1_1") (pintype "passive"))
      (node (ref "POWER0") (pin "2") (pinfunction "2_2") (pintype "passive"))
      (node (ref "POWER1") (pin "1") (pinfunction "1_1") (pintype "power_in"))
      (node (ref "POWER1") (pin "1A") (pinfunction "1A_1A") (pintype "power_in"))
      (node (ref "POWER1") (pin "1B") (pinfunction "1B_1B") (pintype "power_in"))
      (node (ref "S1") (pin "3") (pinfunction "3_3") (pintype "passive"))
    )
    (net (code "40") (name "Net-(U2-XIN{slash}CLK)") (class "Default")
      (node (ref "U2") (pin "1") (pinfunction "XIN/CLK_1") (pintype "passive"))
      (node (ref "XO1") (pin "3") (pinfunction "O/P_3") (pintype "passive"))
    )
    (net (code "41") (name "Net-(U2-Y1)") (class "Default")
      (node (ref "R11") (pin "2") (pinfunction "2_2") (pintype "passive"))
      (node (ref "U2") (pin "11") (pinfunction "Y1_11") (pintype "passive"))
    )
    (net (code "42") (name "Net-(U6-OE)") (class "Default")
      (node (ref "R3") (pin "1") (pinfunction "1_1") (pintype "passive"))
      (node (ref "R7") (pin "2") (pinfunction "2_2") (pintype "passive"))
      (node (ref "U6") (pin "8") (pinfunction "OE_8") (pintype "open_collector"))
    )
    (net (code "43") (name "Net-(U7-OE)") (class "Default")
      (node (ref "R4") (pin "1") (pinfunction "1_1") (pintype "passive"))
      (node (ref "R8") (pin "2") (pinfunction "2_2") (pintype "passive"))
      (node (ref "U7") (pin "8") (pinfunction "OE_8") (pintype "open_collector"))
    )
    (net (code "44") (name "Net-(U20-OE)") (class "Default")
      (node (ref "R1") (pin "1") (pinfunction "1_1") (pintype "passive"))
      (node (ref "R5") (pin "2") (pinfunction "2_2") (pintype "passive"))
      (node (ref "U20") (pin "8") (pinfunction "OE_8") (pintype "open_collector"))
    )
    (net (code "45") (name "Net-(U21-OE)") (class "Default")
      (node (ref "R2") (pin "1") (pinfunction "1_1") (pintype "passive"))
      (node (ref "R6") (pin "2") (pinfunction "2_2") (pintype "passive"))
      (node (ref "U21") (pin "8") (pinfunction "OE_8") (pintype "open_collector"))
    )
    (net (code "46") (name "Net-(U22-BOOT)") (class "Default")
      (node (ref "R36") (pin "1") (pinfunction "1_1") (pintype "passive"))
      (node (ref "U22") (pin "8") (pinfunction "BOOT_8") (pintype "open_collector"))
    )
    (net (code "47") (name "Net-(U22-BP5)") (class "Default")
      (node (ref "C234") (pin "2") (pinfunction "2_2") (pintype "passive"))
      (node (ref "R35") (pin "2") (pinfunction "2_2") (pintype "passive"))
      (node (ref "U22") (pin "6") (pinfunction "BP5_6") (pintype "open_collector"))
    )
    (net (code "48") (name "Net-(U22-COMP)") (class "Default")
      (node (ref "C232") (pin "2") (pinfunction "2_2") (pintype "passive"))
      (node (ref "C233") (pin "2") (pinfunction "2_2") (pintype "passive"))
      (node (ref "R33") (pin "1") (pinfunction "1_1") (pintype "passive"))
      (node (ref "U22") (pin "3") (pinfunction "COMP_3") (pintype "open_collector"))
    )
    (net (code "49") (name "Net-(U22-EN)") (class "Default")
      (node (ref "R34") (pin "1") (pinfunction "1_1") (pintype "passive"))
      (node (ref "U22") (pin "1") (pinfunction "EN_1") (pintype "open_collector"))
    )
    (net (code "50") (name "Net-(U22-FB)") (class "Default")
      (node (ref "C233") (pin "1") (pinfunction "1_1") (pintype "passive"))
      (node (ref "R29") (pin "2") (pinfunction "2_2") (pintype "passive"))
      (node (ref "R30") (pin "1") (pinfunction "1_1") (pintype "passive"))
      (node (ref "R31") (pin "1") (pinfunction "1_1") (pintype "passive"))
      (node (ref "R32") (pin "2") (pinfunction "2_2") (pintype "passive"))
      (node (ref "U22") (pin "2") (pinfunction "FB_2") (pintype "open_collector"))
    )
    (net (code "51") (name "Net-(U22-HDRV)") (class "Default")
      (node (ref "U22") (pin "10") (pinfunction "HDRV_10") (pintype "open_collector"))
      (node (ref "U28") (pin "4") (pinfunction "G_4") (pintype "open_collector"))
    )
    (net (code "52") (name "Net-(U22-LDRV)") (class "Default")
      (node (ref "U22") (pin "7") (pinfunction "LDRV_7") (pintype "open_collector"))
      (node (ref "U27") (pin "4") (pinfunction "G_4") (pintype "open_collector"))
    )
    (net (code "53") (name "Net-(U22-PGD)") (class "Default")
      (node (ref "R35") (pin "1") (pinfunction "1_1") (pintype "passive"))
      (node (ref "U22") (pin "5") (pinfunction "PGD_5") (pintype "open_collector"))
    )
    (net (code "54") (name "Net-(U22-SW)") (class "Default")
      (node (ref "C235") (pin "1") (pinfunction "1_1") (pintype "passive"))
      (node (ref "L4") (pin "1") (pinfunction "1_1") (pintype "passive"))
      (node (ref "U22") (pin "9") (pinfunction "SW_9") (pintype "open_collector"))
      (node (ref "U27") (pin "5") (pinfunction "D_5") (pintype "open_collector"))
      (node (ref "U27") (pin "6") (pinfunction "D_6") (pintype "open_collector"))
      (node (ref "U27") (pin "7") (pinfunction "D_7") (pintype "open_collector"))
      (node (ref "U27") (pin "8") (pinfunction "D_8") (pintype "open_collector"))
      (node (ref "U28") (pin "1") (pinfunction "S_1") (pintype "open_collector"))
      (node (ref "U28") (pin "2") (pinfunction "S_2") (pintype "open_collector"))
      (node (ref "U28") (pin "3") (pinfunction "S_3") (pintype "open_collector"))
    )
    (net (code "55") (name "Net-(U22-VDD)") (class "Default")
      (node (ref "C230") (pin "2") (pinfunction "2_2") (pintype "passive"))
      (node (ref "R28") (pin "1") (pinfunction "1_1") (pintype "passive"))
      (node (ref "U22") (pin "4") (pinfunction "VDD_4") (pintype "open_collector"))
    )
    (net (code "56") (name "Net-(U31-BOOT)") (class "Default")
      (node (ref "R45") (pin "1") (pinfunction "1_1") (pintype "passive"))
      (node (ref "U31") (pin "8") (pinfunction "BOOT_8") (pintype "open_collector"))
    )
    (net (code "57") (name "Net-(U31-BP5)") (class "Default")
      (node (ref "C244") (pin "2") (pinfunction "2_2") (pintype "passive"))
      (node (ref "R44") (pin "2") (pinfunction "2_2") (pintype "passive"))
      (node (ref "U31") (pin "6") (pinfunction "BP5_6") (pintype "open_collector"))
    )
    (net (code "58") (name "Net-(U31-COMP)") (class "Default")
      (node (ref "C241") (pin "2") (pinfunction "2_2") (pintype "passive"))
      (node (ref "C242") (pin "2") (pinfunction "2_2") (pintype "passive"))
      (node (ref "R43") (pin "1") (pinfunction "1_1") (pintype "passive"))
      (node (ref "U31") (pin "3") (pinfunction "COMP_3") (pintype "open_collector"))
    )
    (net (code "59") (name "Net-(U31-EN)") (class "Default")
      (node (ref "R46") (pin "1") (pinfunction "1_1") (pintype "passive"))
      (node (ref "U31") (pin "1") (pinfunction "EN_1") (pintype "open_collector"))
    )
    (net (code "60") (name "Net-(U31-FB)") (class "Default")
      (node (ref "C242") (pin "1") (pinfunction "1_1") (pintype "passive"))
      (node (ref "R39") (pin "2") (pinfunction "2_2") (pintype "passive"))
      (node (ref "R40") (pin "1") (pinfunction "1_1") (pintype "passive"))
      (node (ref "R41") (pin "1") (pinfunction "1_1") (pintype "passive"))
      (node (ref "R42") (pin "2") (pinfunction "2_2") (pintype "passive"))
      (node (ref "U31") (pin "2") (pinfunction "FB_2") (pintype "open_collector"))
    )
    (net (code "61") (name "Net-(U31-HDRV)") (class "Default")
      (node (ref "U31") (pin "10") (pinfunction "HDRV_10") (pintype "open_collector"))
      (node (ref "U33") (pin "4") (pinfunction "G_4") (pintype "open_collector"))
    )
    (net (code "62") (name "Net-(U31-LDRV)") (class "Default")
      (node (ref "U31") (pin "7") (pinfunction "LDRV_7") (pintype "open_collector"))
      (node (ref "U32") (pin "4") (pinfunction "G_4") (pintype "open_collector"))
    )
    (net (code "63") (name "Net-(U31-PGD)") (class "Default")
      (node (ref "R44") (pin "1") (pinfunction "1_1") (pintype "passive"))
      (node (ref "U31") (pin "5") (pinfunction "PGD_5") (pintype "open_collector"))
    )
    (net (code "64") (name "Net-(U31-SW)") (class "Default")
      (node (ref "C245") (pin "1") (pinfunction "1_1") (pintype "passive"))
      (node (ref "L5") (pin "1") (pinfunction "1_1") (pintype "passive"))
      (node (ref "U31") (pin "9") (pinfunction "SW_9") (pintype "open_collector"))
      (node (ref "U32") (pin "5") (pinfunction "D_5") (pintype "open_collector"))
      (node (ref "U32") (pin "6") (pinfunction "D_6") (pintype "open_collector"))
      (node (ref "U32") (pin "7") (pinfunction "D_7") (pintype "open_collector"))
      (node (ref "U32") (pin "8") (pinfunction "D_8") (pintype "open_collector"))
      (node (ref "U33") (pin "1") (pinfunction "S_1") (pintype "open_collector"))
      (node (ref "U33") (pin "2") (pinfunction "S_2") (pintype "open_collector"))
      (node (ref "U33") (pin "3") (pinfunction "S_3") (pintype "open_collector"))
    )
    (net (code "65") (name "Net-(U31-VDD)") (class "Default")
      (node (ref "C240") (pin "2") (pinfunction "2_2") (pintype "passive"))
      (node (ref "R38") (pin "1") (pinfunction "1_1") (pintype "passive"))
      (node (ref "U31") (pin "4") (pinfunction "VDD_4") (pintype "open_collector"))
    )
    (net (code "66") (name "VCC1V8") (class "Default")
      (node (ref "C11") (pin "2") (pinfunction "2_2") (pintype "passive"))
      (node (ref "C12") (pin "2") (pinfunction "2_2") (pintype "passive"))
      (node (ref "C13") (pin "1") (pinfunction "1_1") (pintype "passive"))
      (node (ref "C14") (pin "2") (pinfunction "2_2") (pintype "passive"))
      (node (ref "C2") (pin "1") (pinfunction "1_1") (pintype "passive"))
      (node (ref "C231") (pin "2") (pinfunction "2_2") (pintype "passive"))
      (node (ref "C236") (pin "2") (pinfunction "2_2") (pintype "passive"))
      (node (ref "C237") (pin "2") (pinfunction "2_2") (pintype "passive"))
      (node (ref "C4") (pin "1") (pinfunction "1_1") (pintype "passive"))
      (node (ref "C6") (pin "1") (pinfunction "1_1") (pintype "passive"))
      (node (ref "C8") (pin "1") (pinfunction "1_1") (pintype "passive"))
      (node (ref "L4") (pin "2") (pinfunction "2_2") (pintype "passive"))
      (node (ref "P1") (pin "10") (pinfunction "10_10") (pintype "passive"))
      (node (ref "P2") (pin "10") (pinfunction "10_10") (pintype "passive"))
      (node (ref "P3") (pin "10") (pinfunction "10_10") (pintype "passive"))
      (node (ref "P4") (pin "10") (pinfunction "10_10") (pintype "passive"))
      (node (ref "R31") (pin "2") (pinfunction "2_2") (pintype "passive"))
      (node (ref "U2") (pin "3") (pinfunction "VDD_3") (pintype "passive"))
      (node (ref "U2") (pin "4") (pinfunction "VCTR_4") (pintype "passive"))
      (node (ref "U20") (pin "1") (pinfunction "VCCA_1") (pintype "open_collector"))
      (node (ref "U21") (pin "1") (pinfunction "VCCA_1") (pintype "open_collector"))
      (node (ref "U6") (pin "1") (pinfunction "VCCA_1") (pintype "open_collector"))
      (node (ref "U7") (pin "1") (pinfunction "VCCA_1") (pintype "open_collector"))
      (node (ref "VCC1.8V /20A") (pin "1") (pinfunction "TP_1") (pintype "passive"))
      (node (ref "XO1") (pin "1") (pinfunction "E/~{D}_1") (pintype "passive"))
      (node (ref "XO1") (pin "4") (pinfunction "VDD_4") (pintype "passive"))
    )
    (net (code "67") (name "VCC12V") (class "Default")
      (node (ref "C238") (pin "2") (pinfunction "2_2") (pintype "passive"))
      (node (ref "C239") (pin "2") (pinfunction "2_2") (pintype "passive"))
      (node (ref "C248") (pin "2") (pinfunction "2_2") (pintype "passive"))
      (node (ref "C249") (pin "2") (pinfunction "2_2") (pintype "passive"))
      (node (ref "F1") (pin "1") (pinfunction "1_1") (pintype "passive"))
      (node (ref "R28") (pin "2") (pinfunction "2_2") (pintype "passive"))
      (node (ref "R34") (pin "2") (pinfunction "2_2") (pintype "passive"))
      (node (ref "R37") (pin "2") (pinfunction "2_2") (pintype "passive"))
      (node (ref "R38") (pin "2") (pinfunction "2_2") (pintype "passive"))
      (node (ref "R46") (pin "2") (pinfunction "2_2") (pintype "passive"))
      (node (ref "U28") (pin "5") (pinfunction "D_5") (pintype "open_collector"))
      (node (ref "U28") (pin "6") (pinfunction "D_6") (pintype "open_collector"))
      (node (ref "U28") (pin "7") (pinfunction "D_7") (pintype "open_collector"))
      (node (ref "U28") (pin "8") (pinfunction "D_8") (pintype "open_collector"))
      (node (ref "U33") (pin "5") (pinfunction "D_5") (pintype "open_collector"))
      (node (ref "U33") (pin "6") (pinfunction "D_6") (pintype "open_collector"))
      (node (ref "U33") (pin "7") (pinfunction "D_7") (pintype "open_collector"))
      (node (ref "U33") (pin "8") (pinfunction "D_8") (pintype "open_collector"))
    )
    (net (code "68") (name "unconnected-(P17-Pad7)") (class "Default")
      (node (ref "P17") (pin "7") (pinfunction "7_7") (pintype "passive"))
    )
    (net (code "69") (name "unconnected-(P17-Pad8)") (class "Default")
      (node (ref "P17") (pin "8") (pinfunction "8_8") (pintype "passive"))
    )
    (net (code "70") (name "unconnected-(P17-Pad10)") (class "Default")
      (node (ref "P17") (pin "10") (pinfunction "10_10") (pintype "passive"))
    )
    (net (code "71") (name "unconnected-(P17-Pad11)") (class "Default")
      (node (ref "P17") (pin "11") (pinfunction "11_11") (pintype "passive"))
    )
    (net (code "72") (name "unconnected-(P17-Pad13)") (class "Default")
      (node (ref "P17") (pin "13") (pinfunction "13_13") (pintype "passive"))
    )
    (net (code "73") (name "unconnected-(P17-Pad17)") (class "Default")
      (node (ref "P17") (pin "17") (pinfunction "17_17") (pintype "passive"))
    )
    (net (code "74") (name "unconnected-(P17-Pad24)") (class "Default")
      (node (ref "P17") (pin "24") (pinfunction "24_24") (pintype "passive"))
    )
    (net (code "75") (name "unconnected-(P17-Pad26)") (class "Default")
      (node (ref "P17") (pin "26") (pinfunction "26_26") (pintype "passive"))
    )
    (net (code "76") (name "unconnected-(S1-Pad1)") (class "Default")
      (node (ref "S1") (pin "1") (pinfunction "1_1") (pintype "passive"))
    )
    (net (code "77") (name "unconnected-(U2-S0-Pad2)") (class "Default")
      (node (ref "U2") (pin "2") (pinfunction "S0_2") (pintype "passive"))
    )
    (net (code "78") (name "unconnected-(U2-XOUT-Pad14)") (class "Default")
      (node (ref "U2") (pin "14") (pinfunction "XOUT_14") (pintype "passive"))
    )
    (net (code "79") (name "unconnected-(U2-Y2-Pad9)") (class "Default")
      (node (ref "U2") (pin "9") (pinfunction "Y2_9") (pintype "passive"))
    )
    (net (code "80") (name "unconnected-(U2-Y3-Pad8)") (class "Default")
      (node (ref "U2") (pin "8") (pinfunction "Y3_8") (pintype "passive"))
    )
    (net (code "81") (name "unconnected-(U6-NC-Pad6)") (class "Default")
      (node (ref "U6") (pin "6") (pinfunction "NC_6") (pintype "open_collector"))
    )
    (net (code "82") (name "unconnected-(U6-NC-Pad9)") (class "Default")
      (node (ref "U6") (pin "9") (pinfunction "NC_9") (pintype "open_collector"))
    )
    (net (code "83") (name "unconnected-(U7-NC-Pad6)") (class "Default")
      (node (ref "U7") (pin "6") (pinfunction "NC_6") (pintype "open_collector"))
    )
    (net (code "84") (name "unconnected-(U7-NC-Pad9)") (class "Default")
      (node (ref "U7") (pin "9") (pinfunction "NC_9") (pintype "open_collector"))
    )
    (net (code "85") (name "unconnected-(U20-NC-Pad6)") (class "Default")
      (node (ref "U20") (pin "6") (pinfunction "NC_6") (pintype "open_collector"))
    )
    (net (code "86") (name "unconnected-(U20-NC-Pad9)") (class "Default")
      (node (ref "U20") (pin "9") (pinfunction "NC_9") (pintype "open_collector"))
    )
    (net (code "87") (name "unconnected-(U21-NC-Pad6)") (class "Default")
      (node (ref "U21") (pin "6") (pinfunction "NC_6") (pintype "open_collector"))
    )
    (net (code "88") (name "unconnected-(U21-NC-Pad9)") (class "Default")
      (node (ref "U21") (pin "9") (pinfunction "NC_9") (pintype "open_collector"))
    )
  )
)
